# rc2014_rruart.net
KiCad netlist of a schematic drawn in EAGLE
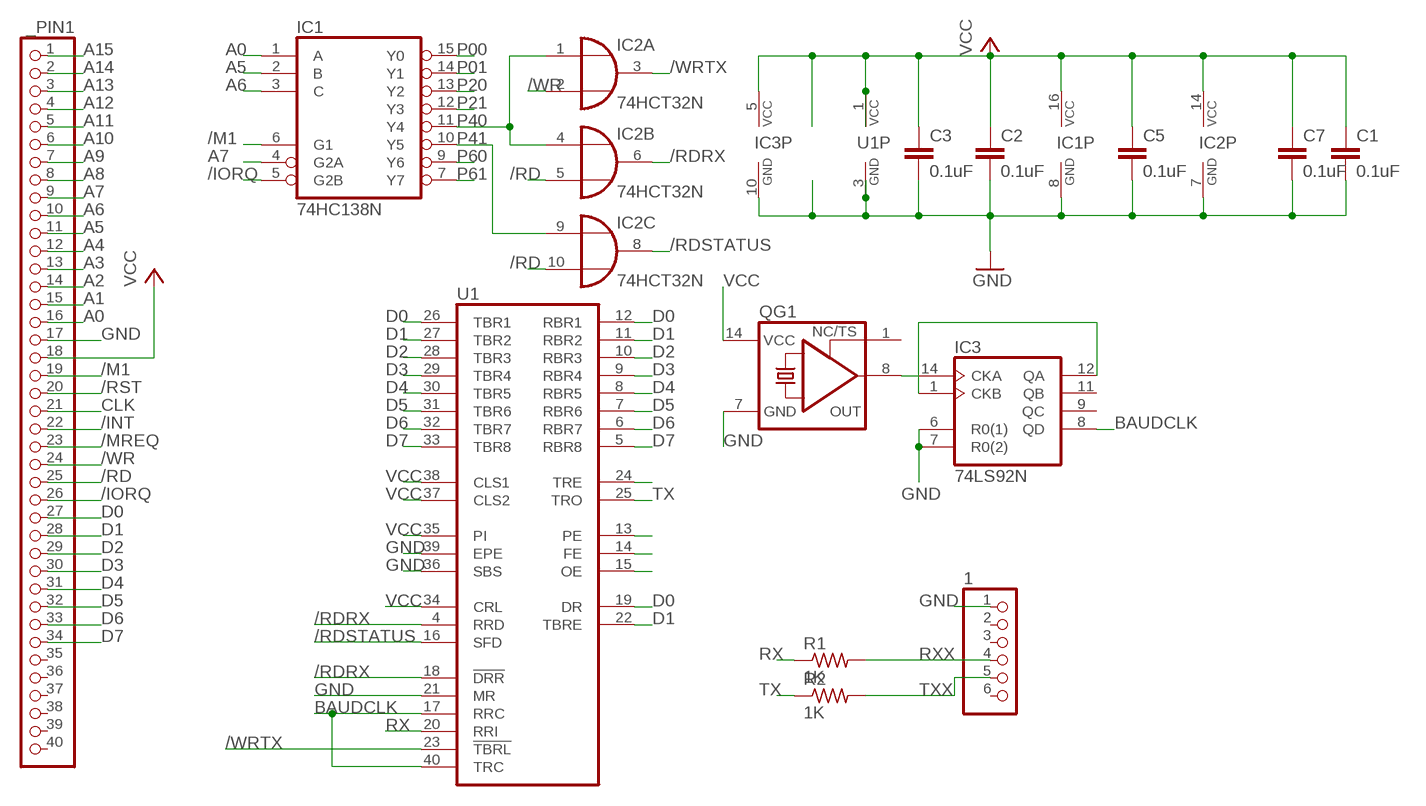
[diagram p0: schematic, sheet 1]

(export (version "E")
  (design (tool "Eeschema 10.0.6"))
  (components
    (comp (ref "1")
      (value "PINHD-1X6")
      (footprint "eagle-import:1X06")
      (libsource (lib "eagle-import") (part "PINHD-1X6"))
    )
    (comp (ref "C1")
      (value "0.1uF")
      (footprint "eagle-import:C050-024X044")
      (libsource (lib "eagle-import") (part "C-EU050-024X044"))
    )
    (comp (ref "C2")
      (value "0.1uF")
      (footprint "eagle-import:C050-024X044")
      (libsource (lib "eagle-import") (part "C-EU050-024X044"))
    )
    (comp (ref "C3")
      (value "0.1uF")
      (footprint "eagle-import:C050-024X044")
      (libsource (lib "eagle-import") (part "C-EU050-024X044"))
    )
    (comp (ref "C5")
      (value "0.1uF")
      (footprint "eagle-import:C050-024X044")
      (libsource (lib "eagle-import") (part "C-EU050-024X044"))
    )
    (comp (ref "C7")
      (value "0.1uF")
      (footprint "eagle-import:C050-024X044")
      (libsource (lib "eagle-import") (part "C-EU050-024X044"))
    )
    (comp (ref "IC1")
      (value "74HC138N")
      (footprint "eagle-import:DIL16")
      (libsource (lib "eagle-import") (part "74138NHC"))
    )
    (comp (ref "IC2")
      (value "74HCT32N")
      (footprint "eagle-import:DIL14")
      (libsource (lib "eagle-import") (part "7432NHCT"))
    )
    (comp (ref "IC3")
      (value "74LS92N")
      (footprint "eagle-import:DIL14")
      (libsource (lib "eagle-import") (part "7492NLS"))
    )
    (comp (ref "QG1")
      (value "XO-14")
      (footprint "eagle-import:DIL14S")
      (libsource (lib "eagle-import") (part "XO-14"))
    )
    (comp (ref "R1")
      (value "1K")
      (footprint "eagle-import:0207_10")
      (libsource (lib "eagle-import") (part "R-US_0207/10"))
    )
    (comp (ref "R2")
      (value "1K")
      (footprint "eagle-import:0207_10")
      (libsource (lib "eagle-import") (part "R-US_0207/10"))
    )
    (comp (ref "U1")
      (value "HD6402")
      (footprint "eagle-import:DIL40")
      (libsource (lib "eagle-import") (part "HD6402"))
    )
    (comp (ref "_PIN1")
      (value "PINHD-1X40")
      (footprint "eagle-import:1X40")
      (libsource (lib "eagle-import") (part "PINHD-1X40"))
    )
  )
  (nets
    (net (code "1") (name "/A0") (class "Default")
      (node (ref "IC1") (pin "1") (pinfunction "A_1") (pintype "input"))
      (node (ref "_PIN1") (pin "16") (pinfunction "16_16") (pintype "passive"))
    )
    (net (code "2") (name "/A1") (class "Default")
      (node (ref "_PIN1") (pin "15") (pinfunction "15_15") (pintype "passive"))
    )
    (net (code "3") (name "/A2") (class "Default")
      (node (ref "_PIN1") (pin "14") (pinfunction "14_14") (pintype "passive"))
    )
    (net (code "4") (name "/A3") (class "Default")
      (node (ref "_PIN1") (pin "13") (pinfunction "13_13") (pintype "passive"))
    )
    (net (code "5") (name "/A4") (class "Default")
      (node (ref "_PIN1") (pin "12") (pinfunction "12_12") (pintype "passive"))
    )
    (net (code "6") (name "/A5") (class "Default")
      (node (ref "IC1") (pin "2") (pinfunction "B_2") (pintype "input"))
      (node (ref "_PIN1") (pin "11") (pinfunction "11_11") (pintype "passive"))
    )
    (net (code "7") (name "/A6") (class "Default")
      (node (ref "IC1") (pin "3") (pinfunction "C_3") (pintype "input"))
      (node (ref "_PIN1") (pin "10") (pinfunction "10_10") (pintype "passive"))
    )
    (net (code "8") (name "/A7") (class "Default")
      (node (ref "IC1") (pin "4") (pinfunction "G2A_4") (pintype "input"))
      (node (ref "_PIN1") (pin "9") (pinfunction "9_9") (pintype "passive"))
    )
    (net (code "9") (name "/A8") (class "Default")
      (node (ref "_PIN1") (pin "8") (pinfunction "8_8") (pintype "passive"))
    )
    (net (code "10") (name "/A9") (class "Default")
      (node (ref "_PIN1") (pin "7") (pinfunction "7_7") (pintype "passive"))
    )
    (net (code "11") (name "/A10") (class "Default")
      (node (ref "_PIN1") (pin "6") (pinfunction "6_6") (pintype "passive"))
    )
    (net (code "12") (name "/A11") (class "Default")
      (node (ref "_PIN1") (pin "5") (pinfunction "5_5") (pintype "passive"))
    )
    (net (code "13") (name "/A12") (class "Default")
      (node (ref "_PIN1") (pin "4") (pinfunction "4_4") (pintype "passive"))
    )
    (net (code "14") (name "/A13") (class "Default")
      (node (ref "_PIN1") (pin "3") (pinfunction "3_3") (pintype "passive"))
    )
    (net (code "15") (name "/A14") (class "Default")
      (node (ref "_PIN1") (pin "2") (pinfunction "2_2") (pintype "passive"))
    )
    (net (code "16") (name "/A15") (class "Default")
      (node (ref "_PIN1") (pin "1") (pinfunction "1_1") (pintype "passive"))
    )
    (net (code "17") (name "/BAUDCLK") (class "Default")
      (node (ref "IC3") (pin "8") (pinfunction "QD_8") (pintype "output"))
      (node (ref "U1") (pin "17") (pinfunction "RRC_17") (pintype "input"))
      (node (ref "U1") (pin "40") (pinfunction "TRC_40") (pintype "input"))
    )
    (net (code "18") (name "/CLK") (class "Default")
      (node (ref "_PIN1") (pin "21") (pinfunction "21_21") (pintype "passive"))
    )
    (net (code "19") (name "/D0") (class "Default")
      (node (ref "U1") (pin "12") (pinfunction "RBR1_12") (pintype "tri_state"))
      (node (ref "U1") (pin "19") (pinfunction "DR_19") (pintype "tri_state"))
      (node (ref "U1") (pin "26") (pinfunction "TBR1_26") (pintype "input"))
      (node (ref "_PIN1") (pin "27") (pinfunction "27_27") (pintype "passive"))
    )
    (net (code "20") (name "/D1") (class "Default")
      (node (ref "U1") (pin "11") (pinfunction "RBR2_11") (pintype "tri_state"))
      (node (ref "U1") (pin "22") (pinfunction "TBRE_22") (pintype "tri_state"))
      (node (ref "U1") (pin "27") (pinfunction "TBR2_27") (pintype "input"))
      (node (ref "_PIN1") (pin "28") (pinfunction "28_28") (pintype "passive"))
    )
    (net (code "21") (name "/D2") (class "Default")
      (node (ref "U1") (pin "10") (pinfunction "RBR3_10") (pintype "tri_state"))
      (node (ref "U1") (pin "28") (pinfunction "TBR3_28") (pintype "input"))
      (node (ref "_PIN1") (pin "29") (pinfunction "29_29") (pintype "passive"))
    )
    (net (code "22") (name "/D3") (class "Default")
      (node (ref "U1") (pin "29") (pinfunction "TBR4_29") (pintype "input"))
      (node (ref "U1") (pin "9") (pinfunction "RBR4_9") (pintype "tri_state"))
      (node (ref "_PIN1") (pin "30") (pinfunction "30_30") (pintype "passive"))
    )
    (net (code "23") (name "/D4") (class "Default")
      (node (ref "U1") (pin "30") (pinfunction "TBR5_30") (pintype "input"))
      (node (ref "U1") (pin "8") (pinfunction "RBR5_8") (pintype "tri_state"))
      (node (ref "_PIN1") (pin "31") (pinfunction "31_31") (pintype "passive"))
    )
    (net (code "24") (name "/D5") (class "Default")
      (node (ref "U1") (pin "31") (pinfunction "TBR6_31") (pintype "input"))
      (node (ref "U1") (pin "7") (pinfunction "RBR6_7") (pintype "tri_state"))
      (node (ref "_PIN1") (pin "32") (pinfunction "32_32") (pintype "passive"))
    )
    (net (code "25") (name "/D6") (class "Default")
      (node (ref "U1") (pin "32") (pinfunction "TBR7_32") (pintype "input"))
      (node (ref "U1") (pin "6") (pinfunction "RBR7_6") (pintype "tri_state"))
      (node (ref "_PIN1") (pin "33") (pinfunction "33_33") (pintype "passive"))
    )
    (net (code "26") (name "/D7") (class "Default")
      (node (ref "U1") (pin "33") (pinfunction "TBR8_33") (pintype "input"))
      (node (ref "U1") (pin "5") (pinfunction "RBR8_5") (pintype "tri_state"))
      (node (ref "_PIN1") (pin "34") (pinfunction "34_34") (pintype "passive"))
    )
    (net (code "27") (name "/P00") (class "Default")
      (node (ref "IC1") (pin "15") (pinfunction "Y0_15") (pintype "output"))
    )
    (net (code "28") (name "/P01") (class "Default")
      (node (ref "IC1") (pin "14") (pinfunction "Y1_14") (pintype "output"))
    )
    (net (code "29") (name "/P20") (class "Default")
      (node (ref "IC1") (pin "13") (pinfunction "Y2_13") (pintype "output"))
    )
    (net (code "30") (name "/P21") (class "Default")
      (node (ref "IC1") (pin "12") (pinfunction "Y3_12") (pintype "output"))
    )
    (net (code "31") (name "/P40") (class "Default")
      (node (ref "IC1") (pin "11") (pinfunction "Y4_11") (pintype "output"))
      (node (ref "IC2") (pin "1") (pinfunction "I0_1") (pintype "input"))
      (node (ref "IC2") (pin "4") (pinfunction "I0_4") (pintype "input"))
    )
    (net (code "32") (name "/P41") (class "Default")
      (node (ref "IC1") (pin "10") (pinfunction "Y5_10") (pintype "output"))
      (node (ref "IC2") (pin "9") (pinfunction "I0_9") (pintype "input"))
    )
    (net (code "33") (name "/P60") (class "Default")
      (node (ref "IC1") (pin "9") (pinfunction "Y6_9") (pintype "output"))
    )
    (net (code "34") (name "/P61") (class "Default")
      (node (ref "IC1") (pin "7") (pinfunction "Y7_7") (pintype "output"))
    )
    (net (code "35") (name "/RX") (class "Default")
      (node (ref "R1") (pin "1") (pinfunction "1_1") (pintype "passive"))
      (node (ref "U1") (pin "20") (pinfunction "RRI_20") (pintype "input"))
    )
    (net (code "36") (name "/RXX") (class "Default")
      (node (ref "1") (pin "4") (pinfunction "4_4") (pintype "passive"))
      (node (ref "R1") (pin "2") (pinfunction "2_2") (pintype "passive"))
    )
    (net (code "37") (name "/TX") (class "Default")
      (node (ref "R2") (pin "1") (pinfunction "1_1") (pintype "passive"))
      (node (ref "U1") (pin "25") (pinfunction "TRO_25") (pintype "output"))
    )
    (net (code "38") (name "/TXX") (class "Default")
      (node (ref "1") (pin "5") (pinfunction "5_5") (pintype "passive"))
      (node (ref "R2") (pin "2") (pinfunction "2_2") (pintype "passive"))
    )
    (net (code "39") (name "/{slash}INT") (class "Default")
      (node (ref "_PIN1") (pin "22") (pinfunction "22_22") (pintype "passive"))
    )
    (net (code "40") (name "/{slash}IORQ") (class "Default")
      (node (ref "IC1") (pin "5") (pinfunction "G2B_5") (pintype "input"))
      (node (ref "_PIN1") (pin "26") (pinfunction "26_26") (pintype "passive"))
    )
    (net (code "41") (name "/{slash}M1") (class "Default")
      (node (ref "IC1") (pin "6") (pinfunction "G1_6") (pintype "input"))
      (node (ref "_PIN1") (pin "19") (pinfunction "19_19") (pintype "passive"))
    )
    (net (code "42") (name "/{slash}MREQ") (class "Default")
      (node (ref "_PIN1") (pin "23") (pinfunction "23_23") (pintype "passive"))
    )
    (net (code "43") (name "/{slash}RD") (class "Default")
      (node (ref "IC2") (pin "10") (pinfunction "I1_10") (pintype "input"))
      (node (ref "IC2") (pin "5") (pinfunction "I1_5") (pintype "input"))
      (node (ref "_PIN1") (pin "25") (pinfunction "25_25") (pintype "passive"))
    )
    (net (code "44") (name "/{slash}RDRX") (class "Default")
      (node (ref "IC2") (pin "6") (pinfunction "O_6") (pintype "output"))
      (node (ref "U1") (pin "18") (pinfunction "~{DRR}_18") (pintype "input"))
      (node (ref "U1") (pin "4") (pinfunction "RRD_4") (pintype "input"))
    )
    (net (code "45") (name "/{slash}RDSTATUS") (class "Default")
      (node (ref "IC2") (pin "8") (pinfunction "O_8") (pintype "output"))
      (node (ref "U1") (pin "16") (pinfunction "SFD_16") (pintype "input"))
    )
    (net (code "46") (name "/{slash}RST") (class "Default")
      (node (ref "_PIN1") (pin "20") (pinfunction "20_20") (pintype "passive"))
    )
    (net (code "47") (name "/{slash}WR") (class "Default")
      (node (ref "IC2") (pin "2") (pinfunction "I1_2") (pintype "input"))
      (node (ref "_PIN1") (pin "24") (pinfunction "24_24") (pintype "passive"))
    )
    (net (code "48") (name "/{slash}WRTX") (class "Default")
      (node (ref "IC2") (pin "3") (pinfunction "O_3") (pintype "output"))
      (node (ref "U1") (pin "23") (pinfunction "~{TBRL}_23") (pintype "input"))
    )
    (net (code "49") (name "GND") (class "Default")
      (node (ref "1") (pin "1") (pinfunction "1_1") (pintype "passive"))
      (node (ref "C1") (pin "2") (pinfunction "2_2") (pintype "passive"))
      (node (ref "C2") (pin "2") (pinfunction "2_2") (pintype "passive"))
      (node (ref "C3") (pin "2") (pinfunction "2_2") (pintype "passive"))
      (node (ref "C5") (pin "2") (pinfunction "2_2") (pintype "passive"))
      (node (ref "C7") (pin "2") (pinfunction "2_2") (pintype "passive"))
      (node (ref "IC1") (pin "8") (pinfunction "GND_8") (pintype "power_in"))
      (node (ref "IC2") (pin "7") (pinfunction "GND_7") (pintype "power_in"))
      (node (ref "IC3") (pin "10") (pinfunction "GND_10") (pintype "power_in"))
      (node (ref "IC3") (pin "6") (pinfunction "R0(1)_6") (pintype "input"))
      (node (ref "IC3") (pin "7") (pinfunction "R0(2)_7") (pintype "input"))
      (node (ref "QG1") (pin "7") (pinfunction "GND_7") (pintype "power_in"))
      (node (ref "U1") (pin "21") (pinfunction "MR_21") (pintype "input"))
      (node (ref "U1") (pin "3") (pinfunction "GND_3") (pintype "power_in"))
      (node (ref "U1") (pin "36") (pinfunction "SBS_36") (pintype "input"))
      (node (ref "U1") (pin "39") (pinfunction "EPE_39") (pintype "input"))
      (node (ref "_PIN1") (pin "17") (pinfunction "17_17") (pintype "passive"))
    )
    (net (code "50") (name "Net-(IC3A-CKA)") (class "Default")
      (node (ref "IC3") (pin "14") (pinfunction "CKA_14") (pintype "input"))
      (node (ref "QG1") (pin "8") (pinfunction "OUT_8") (pintype "output"))
    )
    (net (code "51") (name "Net-(IC3A-CKB)") (class "Default")
      (node (ref "IC3") (pin "1") (pinfunction "CKB_1") (pintype "input"))
      (node (ref "IC3") (pin "12") (pinfunction "QA_12") (pintype "output"))
    )
    (net (code "52") (name "VCC") (class "Default")
      (node (ref "C1") (pin "1") (pinfunction "1_1") (pintype "passive"))
      (node (ref "C2") (pin "1") (pinfunction "1_1") (pintype "passive"))
      (node (ref "C3") (pin "1") (pinfunction "1_1") (pintype "passive"))
      (node (ref "C5") (pin "1") (pinfunction "1_1") (pintype "passive"))
      (node (ref "C7") (pin "1") (pinfunction "1_1") (pintype "passive"))
      (node (ref "IC1") (pin "16") (pinfunction "VCC_16") (pintype "power_in"))
      (node (ref "IC2") (pin "14") (pinfunction "VCC_14") (pintype "power_in"))
      (node (ref "IC3") (pin "5") (pinfunction "VCC_5") (pintype "power_in"))
      (node (ref "QG1") (pin "14") (pinfunction "VCC_14") (pintype "power_in"))
      (node (ref "U1") (pin "1") (pinfunction "VCC_1") (pintype "power_in"))
      (node (ref "U1") (pin "34") (pinfunction "CRL_34") (pintype "input"))
      (node (ref "U1") (pin "35") (pinfunction "PI_35") (pintype "input"))
      (node (ref "U1") (pin "37") (pinfunction "CLS2_37") (pintype "input"))
      (node (ref "U1") (pin "38") (pinfunction "CLS1_38") (pintype "input"))
      (node (ref "_PIN1") (pin "18") (pinfunction "18_18") (pintype "passive"))
    )
    (net (code "53") (name "unconnected-(1-Pad2)") (class "Default")
      (node (ref "1") (pin "2") (pinfunction "2_2") (pintype "passive"))
    )
    (net (code "54") (name "unconnected-(1-Pad3)") (class "Default")
      (node (ref "1") (pin "3") (pinfunction "3_3") (pintype "passive"))
    )
    (net (code "55") (name "unconnected-(1-Pad6)") (class "Default")
      (node (ref "1") (pin "6") (pinfunction "6_6") (pintype "passive"))
    )
    (net (code "56") (name "unconnected-(IC3A-QB-Pad11)") (class "Default")
      (node (ref "IC3") (pin "11") (pinfunction "QB_11") (pintype "output"))
    )
    (net (code "57") (name "unconnected-(IC3A-QC-Pad9)") (class "Default")
      (node (ref "IC3") (pin "9") (pinfunction "QC_9") (pintype "output"))
    )
    (net (code "58") (name "unconnected-(QG1-TS-Pad1)") (class "Default")
      (node (ref "QG1") (pin "1") (pinfunction "TS_1") (pintype "passive"))
    )
    (net (code "59") (name "unconnected-(U1A-FE-Pad14)") (class "Default")
      (node (ref "U1") (pin "14") (pinfunction "FE_14") (pintype "tri_state"))
    )
    (net (code "60") (name "unconnected-(U1A-OE-Pad15)") (class "Default")
      (node (ref "U1") (pin "15") (pinfunction "OE_15") (pintype "tri_state"))
    )
    (net (code "61") (name "unconnected-(U1A-PE-Pad13)") (class "Default")
      (node (ref "U1") (pin "13") (pinfunction "PE_13") (pintype "tri_state"))
    )
    (net (code "62") (name "unconnected-(U1A-TRE-Pad24)") (class "Default")
      (node (ref "U1") (pin "24") (pinfunction "TRE_24") (pintype "output"))
    )
    (net (code "63") (name "unconnected-(_PIN1-Pad35)") (class "Default")
      (node (ref "_PIN1") (pin "35") (pinfunction "35_35") (pintype "passive"))
    )
    (net (code "64") (name "unconnected-(_PIN1-Pad36)") (class "Default")
      (node (ref "_PIN1") (pin "36") (pinfunction "36_36") (pintype "passive"))
    )
    (net (code "65") (name "unconnected-(_PIN1-Pad37)") (class "Default")
      (node (ref "_PIN1") (pin "37") (pinfunction "37_37") (pintype "passive"))
    )
    (net (code "66") (name "unconnected-(_PIN1-Pad38)") (class "Default")
      (node (ref "_PIN1") (pin "38") (pinfunction "38_38") (pintype "passive"))
    )
    (net (code "67") (name "unconnected-(_PIN1-Pad39)") (class "Default")
      (node (ref "_PIN1") (pin "39") (pinfunction "39_39") (pintype "passive"))
    )
    (net (code "68") (name "unconnected-(_PIN1-Pad40)") (class "Default")
      (node (ref "_PIN1") (pin "40") (pinfunction "40_40") (pintype "passive"))
    )
  )
)
